# liuyang.net
KiCad netlist of a schematic drawn in Altium Designer
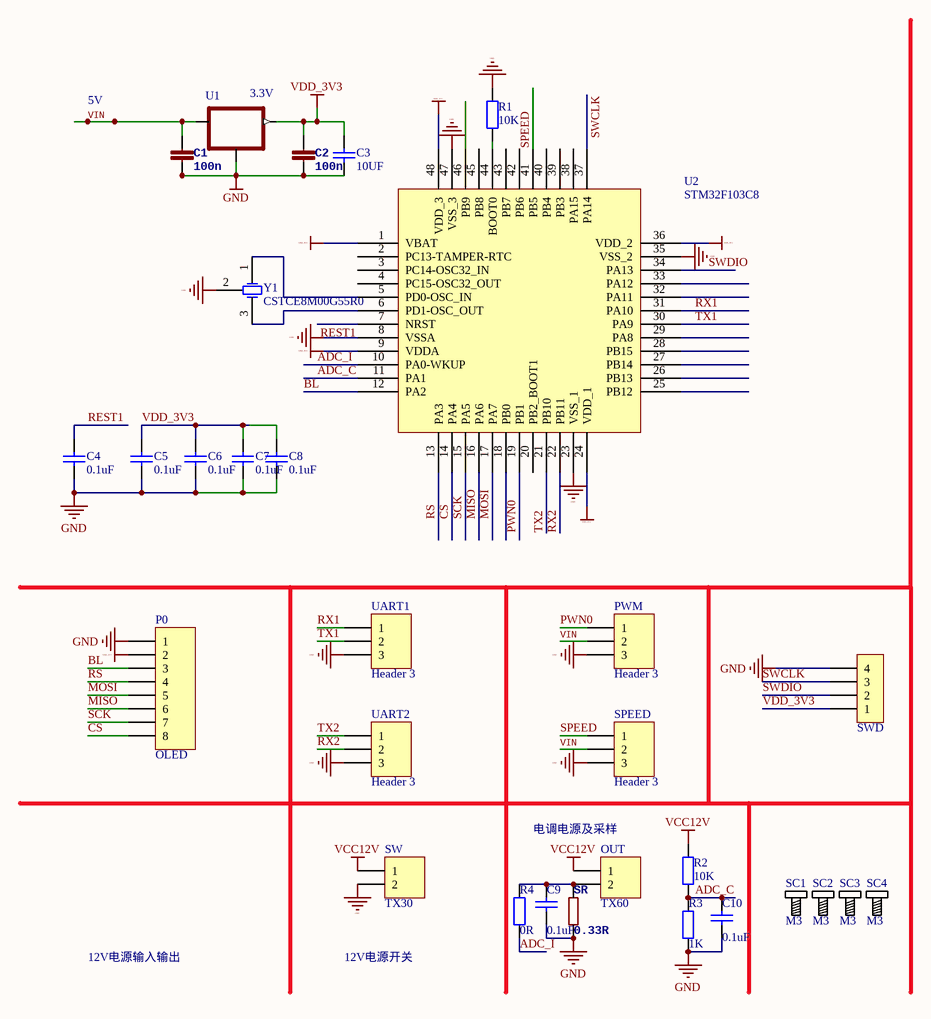
[diagram p0: liuyang.SchDoc]

(export (version "E")
  (design (tool "Eeschema 10.0.6"))
  (components
    (comp (ref "C1")
      (value "100n")
      (footprint "C0603")
      (description "CAPACITOR, European symbol")
      (libsource (lib "rcl") (part "C-EUC0603"))
    )
    (comp (ref "C2")
      (value "100n")
      (footprint "C0603")
      (description "CAPACITOR, European symbol")
      (libsource (lib "rcl") (part "C-EUC0603"))
    )
    (comp (ref "C3")
      (value "10UF")
      (footprint "C0603")
      (description "Capacitor")
      (fields (field (name "PUBLISHER") "Altium Limited"))
      (libsource (lib "Miscellaneous Devices") (part "Cap"))
    )
    (comp (ref "C4")
      (value "0.1uF")
      (footprint "C0603")
      (description "Capacitor")
      (fields (field (name "PUBLISHER") "Altium Limited"))
      (libsource (lib "Miscellaneous Devices") (part "Cap"))
    )
    (comp (ref "C5")
      (value "0.1uF")
      (footprint "C0603")
      (description "Capacitor")
      (fields (field (name "Comment") "10UF") (field (name "PUBLISHER") "Altium Limited"))
      (libsource (lib "Miscellaneous Devices") (part "Cap"))
    )
    (comp (ref "C6")
      (value "0.1uF")
      (footprint "C0603")
      (description "Capacitor")
      (fields (field (name "PUBLISHER") "Altium Limited"))
      (libsource (lib "Miscellaneous Devices") (part "Cap"))
    )
    (comp (ref "C7")
      (value "0.1uF")
      (footprint "C0603")
      (description "Capacitor")
      (fields (field (name "PUBLISHER") "Altium Limited"))
      (libsource (lib "Miscellaneous Devices") (part "Cap"))
    )
    (comp (ref "C8")
      (value "0.1uF")
      (footprint "C0603")
      (description "Capacitor")
      (fields (field (name "PUBLISHER") "Altium Limited"))
      (libsource (lib "Miscellaneous Devices") (part "Cap"))
    )
    (comp (ref "C9")
      (value "0.1uF")
      (footprint "C0603")
      (description "Capacitor")
      (fields (field (name "PUBLISHER") "Altium Limited"))
      (libsource (lib "Miscellaneous Devices") (part "Cap"))
    )
    (comp (ref "C10")
      (value "0.1uF")
      (footprint "C0603")
      (description "Capacitor")
      (fields (field (name "PUBLISHER") "Altium Limited"))
      (libsource (lib "Miscellaneous Devices") (part "Cap"))
    )
    (comp (ref "OUT")
      (value "TX60")
      (footprint "TX30-m")
      (description "Header, 2-Pin")
      (fields (field (name "PUBLISHER") "Altium Limited"))
      (libsource (lib "Miscellaneous Connectors") (part "Header 2"))
    )
    (comp (ref "P0")
      (value "OLED")
      (footprint "DF13-1.25-8A")
      (description "Header, 8-Pin")
      (fields (field (name "PUBLISHER") "Altium Limited"))
      (libsource (lib "Miscellaneous Connectors") (part "Header 8"))
    )
    (comp (ref "PWM")
      (value "Header 3")
      (footprint "DF13-1.25-3A")
      (description "Header, 3-Pin")
      (fields (field (name "PUBLISHER") "Altium Limited"))
      (libsource (lib "Miscellaneous Connectors") (part "Header 3"))
    )
    (comp (ref "R1")
      (value "10K")
      (footprint "R0603")
      (description "Resistor")
      (fields (field (name "PUBLISHER") "Altium Limited"))
      (libsource (lib "Miscellaneous Devices") (part "Res2"))
    )
    (comp (ref "R2")
      (value "10K")
      (footprint "R0603")
      (description "Resistor")
      (fields (field (name "PUBLISHER") "Altium Limited"))
      (libsource (lib "Miscellaneous Devices") (part "Res2"))
    )
    (comp (ref "R3")
      (value "1K")
      (footprint "R0603")
      (description "Resistor")
      (fields (field (name "Comment") "10K") (field (name "PUBLISHER") "Altium Limited"))
      (libsource (lib "Miscellaneous Devices") (part "Res2"))
    )
    (comp (ref "R4")
      (value "0R")
      (footprint "R0603")
      (description "Resistor")
      (fields (field (name "Comment") "10K") (field (name "PUBLISHER") "Altium Limited"))
      (libsource (lib "Miscellaneous Devices") (part "Res2"))
    )
    (comp (ref "SC1")
      (value "M3")
      (footprint "TZJLIB:SCRREW_M3")
      (description "Screw")
      (libsource (lib "MY") (part "Screw_M3"))
    )
    (comp (ref "SC2")
      (value "M3")
      (footprint "SCRREW_M3")
      (description "Screw")
      (libsource (lib "MY") (part "Screw_M3"))
    )
    (comp (ref "SC3")
      (value "M3")
      (footprint "SCRREW_M3")
      (description "Screw")
      (libsource (lib "MY") (part "Screw_M3"))
    )
    (comp (ref "SC4")
      (value "M3")
      (footprint "SCRREW_M3")
      (description "Screw")
      (libsource (lib "MY") (part "Screw_M3"))
    )
    (comp (ref "SPEED")
      (value "Header 3")
      (footprint "DF13-1.25-3A")
      (description "Header, 3-Pin")
      (fields (field (name "PUBLISHER") "Altium Limited"))
      (libsource (lib "Miscellaneous Connectors") (part "Header 3"))
    )
    (comp (ref "SR")
      (value "0.33R")
      (footprint "R2512")
      (description "RESISTOR, European symbol")
      (libsource (lib "rcl") (part "R-EU_R0603"))
    )
    (comp (ref "SW")
      (value "TX30")
      (footprint "TX30-m")
      (description "Header, 2-Pin")
      (fields (field (name "PUBLISHER") "Altium Limited"))
      (libsource (lib "Miscellaneous Connectors") (part "Header 2"))
    )
    (comp (ref "SWD") (value "CON4") (footprint "DF13-1.25-4A") (libsource (lib "原理图封装库") (part "CON4")))
    (comp (ref "U1") (value "3.3V") (footprint "SOT23") (libsource (lib "BGC1.0") (part "XC6206")))
    (comp (ref "U2")
      (value "STM32F103C8")
      (footprint "ST_LQFP48")
      (libsource (lib "airtops-L") (part "STM32F103C8"))
    )
    (comp (ref "UART1")
      (value "Header 3")
      (footprint "DF13-1.25-3A")
      (description "Header, 3-Pin")
      (fields (field (name "PUBLISHER") "Altium Limited"))
      (libsource (lib "Miscellaneous Connectors") (part "Header 3"))
    )
    (comp (ref "UART2")
      (value "Header 3")
      (footprint "DF13-1.25-3A")
      (description "Header, 3-Pin")
      (fields (field (name "PUBLISHER") "Altium Limited"))
      (libsource (lib "Miscellaneous Connectors") (part "Header 3"))
    )
    (comp (ref "Y1")
      (value "CSTCE8M00G55R0")
      (footprint "CRYSMD3.2X1.3")
      (libsource (lib "airtops-L") (part "XTAL-3"))
    )
  )
  (nets
    (net (code "1") (name "/ADC_C") (class "Default")
      (node (ref "C10") (pin "2") (pinfunction "2_2") (pintype "passive"))
      (node (ref "R2") (pin "2") (pinfunction "2_2") (pintype "passive"))
      (node (ref "R3") (pin "1") (pinfunction "1_1") (pintype "passive"))
      (node (ref "U2") (pin "11") (pinfunction "PA1_11") (pintype "passive"))
    )
    (net (code "2") (name "/ADC_I") (class "Default")
      (node (ref "R4") (pin "2") (pinfunction "2_2") (pintype "passive"))
      (node (ref "U2") (pin "10") (pinfunction "PA0-WKUP_10") (pintype "passive"))
    )
    (net (code "3") (name "/BL") (class "Default")
      (node (ref "P0") (pin "3") (pinfunction "3_3") (pintype "passive"))
      (node (ref "U2") (pin "12") (pinfunction "PA2_12") (pintype "passive"))
    )
    (net (code "4") (name "/CS") (class "Default")
      (node (ref "P0") (pin "8") (pinfunction "8_8") (pintype "passive"))
      (node (ref "U2") (pin "14") (pinfunction "PA4_14") (pintype "passive"))
    )
    (net (code "5") (name "/MISO") (class "Default")
      (node (ref "P0") (pin "6") (pinfunction "6_6") (pintype "passive"))
      (node (ref "U2") (pin "16") (pinfunction "PA6_16") (pintype "passive"))
    )
    (net (code "6") (name "/MOSI") (class "Default")
      (node (ref "P0") (pin "5") (pinfunction "5_5") (pintype "passive"))
      (node (ref "U2") (pin "17") (pinfunction "PA7_17") (pintype "passive"))
    )
    (net (code "7") (name "/PWN0") (class "Default")
      (node (ref "PWM") (pin "1") (pinfunction "1_1") (pintype "passive"))
      (node (ref "U2") (pin "19") (pinfunction "PB1_19") (pintype "passive"))
    )
    (net (code "8") (name "/REST1") (class "Default")
      (node (ref "C4") (pin "2") (pinfunction "2_2") (pintype "passive"))
      (node (ref "U2") (pin "7") (pinfunction "NRST_7") (pintype "passive"))
    )
    (net (code "9") (name "/RS") (class "Default")
      (node (ref "P0") (pin "4") (pinfunction "4_4") (pintype "passive"))
      (node (ref "U2") (pin "13") (pinfunction "PA3_13") (pintype "passive"))
    )
    (net (code "10") (name "/RX1") (class "Default")
      (node (ref "U2") (pin "31") (pinfunction "PA10_31") (pintype "passive"))
      (node (ref "UART1") (pin "1") (pinfunction "1_1") (pintype "passive"))
    )
    (net (code "11") (name "/RX2") (class "Default")
      (node (ref "U2") (pin "22") (pinfunction "PB11_22") (pintype "passive"))
      (node (ref "UART2") (pin "2") (pinfunction "2_2") (pintype "passive"))
    )
    (net (code "12") (name "/SCK") (class "Default")
      (node (ref "P0") (pin "7") (pinfunction "7_7") (pintype "passive"))
      (node (ref "U2") (pin "15") (pinfunction "PA5_15") (pintype "passive"))
    )
    (net (code "13") (name "/SPEED") (class "Default")
      (node (ref "SPEED") (pin "1") (pinfunction "1_1") (pintype "passive"))
      (node (ref "U2") (pin "41") (pinfunction "PB5_41") (pintype "passive"))
    )
    (net (code "14") (name "/SWCLK") (class "Default")
      (node (ref "SWD") (pin "3") (pinfunction "3_3") (pintype "passive"))
      (node (ref "U2") (pin "37") (pinfunction "PA14_37") (pintype "passive"))
    )
    (net (code "15") (name "/SWDIO") (class "Default")
      (node (ref "SWD") (pin "2") (pinfunction "2_2") (pintype "passive"))
      (node (ref "U2") (pin "34") (pinfunction "PA13_34") (pintype "passive"))
    )
    (net (code "16") (name "/TX1") (class "Default")
      (node (ref "U2") (pin "30") (pinfunction "PA9_30") (pintype "passive"))
      (node (ref "UART1") (pin "2") (pinfunction "2_2") (pintype "passive"))
    )
    (net (code "17") (name "/TX2") (class "Default")
      (node (ref "U2") (pin "21") (pinfunction "PB10_21") (pintype "passive"))
      (node (ref "UART2") (pin "1") (pinfunction "1_1") (pintype "passive"))
    )
    (net (code "18") (name "/VIN") (class "Default")
      (node (ref "C1") (pin "1") (pinfunction "1_1") (pintype "passive"))
      (node (ref "PWM") (pin "2") (pinfunction "2_2") (pintype "passive"))
      (node (ref "SPEED") (pin "2") (pinfunction "2_2") (pintype "passive"))
      (node (ref "U1") (pin "3") (pinfunction "IN_3") (pintype "passive"))
    )
    (net (code "19") (name "GND") (class "Default")
      (node (ref "C1") (pin "2") (pinfunction "2_2") (pintype "passive"))
      (node (ref "C10") (pin "1") (pinfunction "1_1") (pintype "passive"))
      (node (ref "C2") (pin "2") (pinfunction "2_2") (pintype "passive"))
      (node (ref "C3") (pin "1") (pinfunction "1_1") (pintype "passive"))
      (node (ref "C4") (pin "1") (pinfunction "1_1") (pintype "passive"))
      (node (ref "C5") (pin "1") (pinfunction "1_1") (pintype "passive"))
      (node (ref "C6") (pin "1") (pinfunction "1_1") (pintype "passive"))
      (node (ref "C7") (pin "1") (pinfunction "1_1") (pintype "passive"))
      (node (ref "C8") (pin "1") (pinfunction "1_1") (pintype "passive"))
      (node (ref "C9") (pin "1") (pinfunction "1_1") (pintype "passive"))
      (node (ref "P0") (pin "1") (pinfunction "1_1") (pintype "passive"))
      (node (ref "PWM") (pin "3") (pinfunction "3_3") (pintype "passive"))
      (node (ref "R1") (pin "1") (pinfunction "1_1") (pintype "passive"))
      (node (ref "R3") (pin "2") (pinfunction "2_2") (pintype "passive"))
      (node (ref "SPEED") (pin "3") (pinfunction "3_3") (pintype "passive"))
      (node (ref "SR") (pin "2") (pinfunction "2_2") (pintype "passive"))
      (node (ref "SW") (pin "2") (pinfunction "2_2") (pintype "passive"))
      (node (ref "SWD") (pin "4") (pinfunction "4_4") (pintype "passive"))
      (node (ref "U1") (pin "1") (pinfunction "GND_1") (pintype "passive"))
      (node (ref "U2") (pin "23") (pinfunction "VSS_1_23") (pintype "passive"))
      (node (ref "U2") (pin "35") (pinfunction "VSS_2_35") (pintype "passive"))
      (node (ref "U2") (pin "47") (pinfunction "VSS_3_47") (pintype "passive"))
      (node (ref "U2") (pin "8") (pinfunction "VSSA_8") (pintype "passive"))
      (node (ref "UART1") (pin "3") (pinfunction "3_3") (pintype "passive"))
      (node (ref "UART2") (pin "3") (pinfunction "3_3") (pintype "passive"))
      (node (ref "Y1") (pin "2") (pinfunction "GND_2") (pintype "passive"))
    )
    (net (code "20") (name "Net-(C9-Pad2)") (class "Default")
      (node (ref "C9") (pin "2") (pinfunction "2_2") (pintype "passive"))
      (node (ref "OUT") (pin "2") (pinfunction "2_2") (pintype "passive"))
      (node (ref "R4") (pin "1") (pinfunction "1_1") (pintype "passive"))
      (node (ref "SR") (pin "1") (pinfunction "1_1") (pintype "passive"))
    )
    (net (code "21") (name "Net-(U2-BOOT0)") (class "Default")
      (node (ref "R1") (pin "2") (pinfunction "2_2") (pintype "passive"))
      (node (ref "U2") (pin "44") (pinfunction "BOOT0_44") (pintype "passive"))
    )
    (net (code "22") (name "Net-(U2-PD0-OSC_IN)") (class "Default")
      (node (ref "U2") (pin "5") (pinfunction "PD0-OSC_IN_5") (pintype "passive"))
      (node (ref "Y1") (pin "1") (pinfunction "OSC1_1") (pintype "passive"))
    )
    (net (code "23") (name "Net-(U2-PD1-OSC_OUT)") (class "Default")
      (node (ref "U2") (pin "6") (pinfunction "PD1-OSC_OUT_6") (pintype "passive"))
      (node (ref "Y1") (pin "3") (pinfunction "OSC2_3") (pintype "passive"))
    )
    (net (code "24") (name "VCC12V") (class "Default")
      (node (ref "OUT") (pin "1") (pinfunction "1_1") (pintype "passive"))
      (node (ref "R2") (pin "1") (pinfunction "1_1") (pintype "passive"))
      (node (ref "SW") (pin "1") (pinfunction "1_1") (pintype "passive"))
    )
    (net (code "25") (name "VDD_3V3") (class "Default")
      (node (ref "C2") (pin "1") (pinfunction "1_1") (pintype "passive"))
      (node (ref "C3") (pin "2") (pinfunction "2_2") (pintype "passive"))
      (node (ref "C5") (pin "2") (pinfunction "2_2") (pintype "passive"))
      (node (ref "C6") (pin "2") (pinfunction "2_2") (pintype "passive"))
      (node (ref "C7") (pin "2") (pinfunction "2_2") (pintype "passive"))
      (node (ref "C8") (pin "2") (pinfunction "2_2") (pintype "passive"))
      (node (ref "P0") (pin "2") (pinfunction "2_2") (pintype "passive"))
      (node (ref "SWD") (pin "1") (pinfunction "1_1") (pintype "passive"))
      (node (ref "U1") (pin "2") (pinfunction "OUT_2") (pintype "output"))
      (node (ref "U2") (pin "1") (pinfunction "VBAT_1") (pintype "passive"))
      (node (ref "U2") (pin "24") (pinfunction "VDD_1_24") (pintype "passive"))
      (node (ref "U2") (pin "36") (pinfunction "VDD_2_36") (pintype "passive"))
      (node (ref "U2") (pin "48") (pinfunction "VDD_3_48") (pintype "passive"))
      (node (ref "U2") (pin "9") (pinfunction "VDDA_9") (pintype "passive"))
    )
    (net (code "26") (name "unconnected-(U2-PA8-Pad29)") (class "Default")
      (node (ref "U2") (pin "29") (pinfunction "PA8_29") (pintype "passive"))
    )
    (net (code "27") (name "unconnected-(U2-PA11-Pad32)") (class "Default")
      (node (ref "U2") (pin "32") (pinfunction "PA11_32") (pintype "passive"))
    )
    (net (code "28") (name "unconnected-(U2-PA12-Pad33)") (class "Default")
      (node (ref "U2") (pin "33") (pinfunction "PA12_33") (pintype "passive"))
    )
    (net (code "29") (name "unconnected-(U2-PA15-Pad38)") (class "Default")
      (node (ref "U2") (pin "38") (pinfunction "PA15_38") (pintype "passive"))
    )
    (net (code "30") (name "unconnected-(U2-PB0-Pad18)") (class "Default")
      (node (ref "U2") (pin "18") (pinfunction "PB0_18") (pintype "passive"))
    )
    (net (code "31") (name "unconnected-(U2-PB2_BOOT1-Pad20)") (class "Default")
      (node (ref "U2") (pin "20") (pinfunction "PB2_BOOT1_20") (pintype "passive"))
    )
    (net (code "32") (name "unconnected-(U2-PB3-Pad39)") (class "Default")
      (node (ref "U2") (pin "39") (pinfunction "PB3_39") (pintype "passive"))
    )
    (net (code "33") (name "unconnected-(U2-PB4-Pad40)") (class "Default")
      (node (ref "U2") (pin "40") (pinfunction "PB4_40") (pintype "passive"))
    )
    (net (code "34") (name "unconnected-(U2-PB6-Pad42)") (class "Default")
      (node (ref "U2") (pin "42") (pinfunction "PB6_42") (pintype "passive"))
    )
    (net (code "35") (name "unconnected-(U2-PB7-Pad43)") (class "Default")
      (node (ref "U2") (pin "43") (pinfunction "PB7_43") (pintype "passive"))
    )
    (net (code "36") (name "unconnected-(U2-PB8-Pad45)") (class "Default")
      (node (ref "U2") (pin "45") (pinfunction "PB8_45") (pintype "passive"))
    )
    (net (code "37") (name "unconnected-(U2-PB9-Pad46)") (class "Default")
      (node (ref "U2") (pin "46") (pinfunction "PB9_46") (pintype "passive"))
    )
    (net (code "38") (name "unconnected-(U2-PB12-Pad25)") (class "Default")
      (node (ref "U2") (pin "25") (pinfunction "PB12_25") (pintype "passive"))
    )
    (net (code "39") (name "unconnected-(U2-PB13-Pad26)") (class "Default")
      (node (ref "U2") (pin "26") (pinfunction "PB13_26") (pintype "passive"))
    )
    (net (code "40") (name "unconnected-(U2-PB14-Pad27)") (class "Default")
      (node (ref "U2") (pin "27") (pinfunction "PB14_27") (pintype "passive"))
    )
    (net (code "41") (name "unconnected-(U2-PB15-Pad28)") (class "Default")
      (node (ref "U2") (pin "28") (pinfunction "PB15_28") (pintype "passive"))
    )
    (net (code "42") (name "unconnected-(U2-PC13-TAMPER-RTC-Pad2)") (class "Default")
      (node (ref "U2") (pin "2") (pinfunction "PC13-TAMPER-RTC_2") (pintype "passive"))
    )
    (net (code "43") (name "unconnected-(U2-PC14-OSC32_IN-Pad3)") (class "Default")
      (node (ref "U2") (pin "3") (pinfunction "PC14-OSC32_IN_3") (pintype "passive"))
    )
    (net (code "44") (name "unconnected-(U2-PC15-OSC32_OUT-Pad4)") (class "Default")
      (node (ref "U2") (pin "4") (pinfunction "PC15-OSC32_OUT_4") (pintype "passive"))
    )
  )
)
